# siren.net
KiCad netlist of a schematic drawn in EAGLE
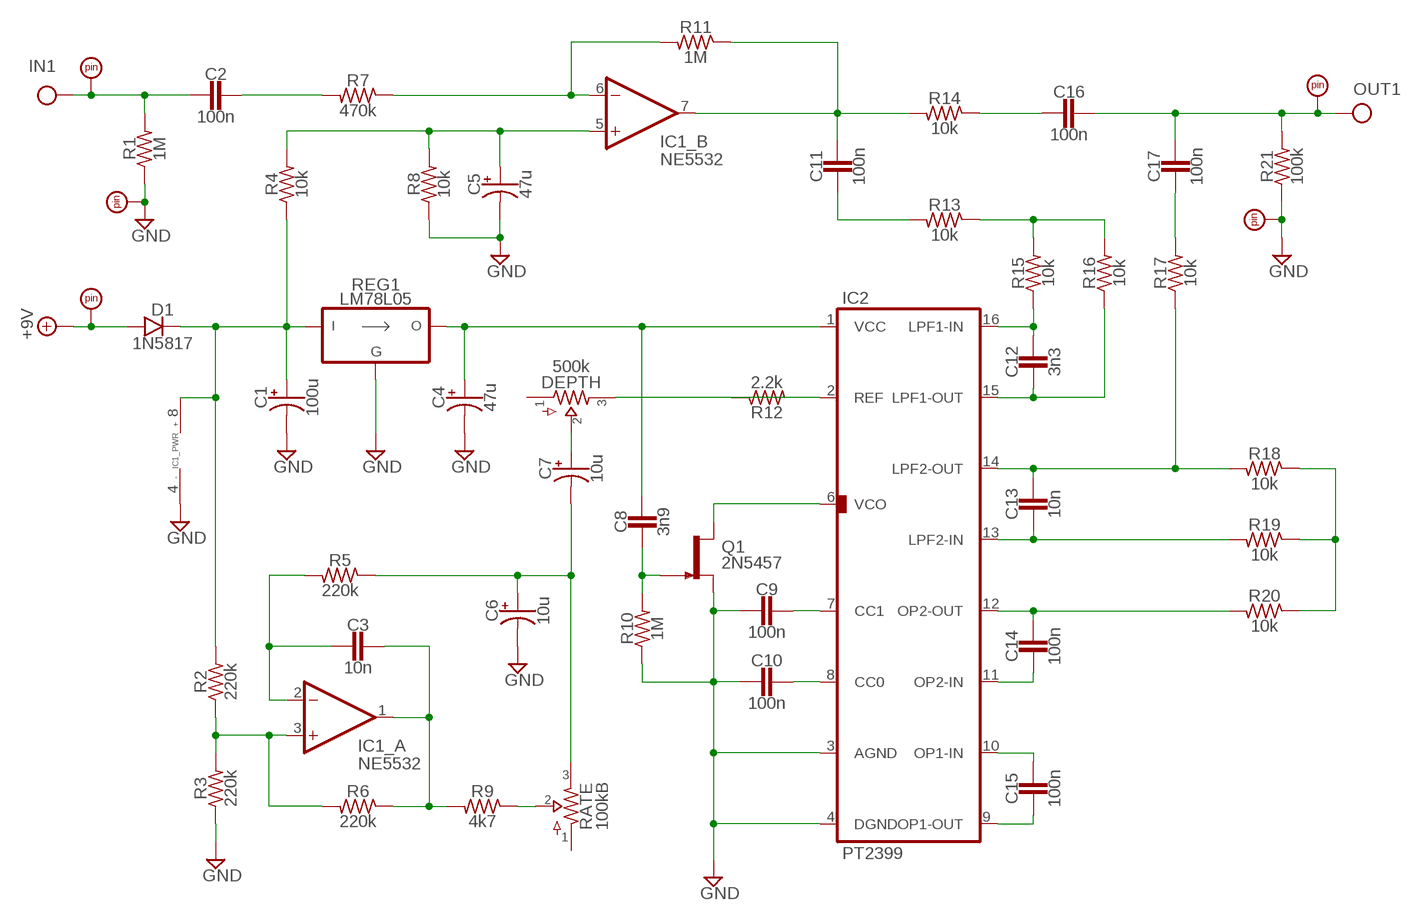
[diagram p0: schematic, sheet 1]

(export (version "E")
  (design (tool "Eeschema 10.0.6"))
  (components
    (comp (ref "C1")
      (value "100u")
      (footprint "eagle-import:050_020_1")
      (libsource (lib "eagle-import") (part "0501"))
    )
    (comp (ref "C2")
      (value "100n")
      (footprint "eagle-import:BOX_SMALL")
      (libsource (lib "eagle-import") (part "CER/FILMBOX.1"))
    )
    (comp (ref "C3")
      (value "10n")
      (footprint "eagle-import:BOX_SMALL")
      (libsource (lib "eagle-import") (part "CER/FILMBOX.1"))
    )
    (comp (ref "C4")
      (value "47u")
      (footprint "eagle-import:050_020_1")
      (libsource (lib "eagle-import") (part "0501"))
    )
    (comp (ref "C5")
      (value "47u")
      (footprint "eagle-import:050_020_1")
      (libsource (lib "eagle-import") (part "0501"))
    )
    (comp (ref "C6")
      (value "10u")
      (footprint "eagle-import:050_020_1")
      (libsource (lib "eagle-import") (part "0501"))
    )
    (comp (ref "C7")
      (value "10u")
      (footprint "eagle-import:050_020_1")
      (libsource (lib "eagle-import") (part "0501"))
    )
    (comp (ref "C8")
      (value "3n9")
      (footprint "eagle-import:BOX_SMALL")
      (libsource (lib "eagle-import") (part "CER/FILMBOX.1"))
    )
    (comp (ref "C9")
      (value "100n")
      (footprint "eagle-import:BOX_SMALL")
      (libsource (lib "eagle-import") (part "CER/FILMBOX.1"))
    )
    (comp (ref "C10")
      (value "100n")
      (footprint "eagle-import:BOX_SMALL")
      (libsource (lib "eagle-import") (part "CER/FILMBOX.1"))
    )
    (comp (ref "C11")
      (value "100n")
      (footprint "eagle-import:BOX_SMALL")
      (libsource (lib "eagle-import") (part "CER/FILMBOX.1"))
    )
    (comp (ref "C12")
      (value "3n3")
      (footprint "eagle-import:BOX_SMALL")
      (libsource (lib "eagle-import") (part "CER/FILMBOX.1"))
    )
    (comp (ref "C13")
      (value "10n")
      (footprint "eagle-import:BOX_SMALL")
      (libsource (lib "eagle-import") (part "CER/FILMBOX.1"))
    )
    (comp (ref "C14")
      (value "100n")
      (footprint "eagle-import:BOX_SMALL")
      (libsource (lib "eagle-import") (part "CER/FILMBOX.1"))
    )
    (comp (ref "C15")
      (value "100n")
      (footprint "eagle-import:BOX_SMALL")
      (libsource (lib "eagle-import") (part "CER/FILMBOX.1"))
    )
    (comp (ref "C16")
      (value "100n")
      (footprint "eagle-import:BOX_SMALL")
      (libsource (lib "eagle-import") (part "CER/FILMBOX.1"))
    )
    (comp (ref "C17")
      (value "100n")
      (footprint "eagle-import:BOX_SMALL")
      (libsource (lib "eagle-import") (part "CER/FILMBOX.1"))
    )
    (comp (ref "D1")
      (value "1N5817")
      (footprint "eagle-import:DO41-2")
      (libsource (lib "eagle-import") (part "DO41.2"))
    )
    (comp (ref "DEPTH")
      (value "500k")
      (footprint "eagle-import:2262_TRIM")
      (libsource (lib "eagle-import") (part "POTSTRIM"))
    )
    (comp (ref "IC1")
      (value "NE5532")
      (footprint "eagle-import:DIL08")
      (libsource (lib "eagle-import") (part "DUALTH"))
    )
    (comp (ref "IC2")
      (value "PT2399")
      (footprint "eagle-import:DIL16")
      (libsource (lib "eagle-import") (part "PT2399TH"))
    )
    (comp (ref "PAD1")
      (value "PADSQR")
      (footprint "eagle-import:SQUARE")
      (libsource (lib "eagle-import") (part "PADSQR"))
    )
    (comp (ref "PAD2")
      (value "PADSQR")
      (footprint "eagle-import:SQUARE")
      (libsource (lib "eagle-import") (part "PADSQR"))
    )
    (comp (ref "PAD3")
      (value "PADRND")
      (footprint "eagle-import:ROUND")
      (libsource (lib "eagle-import") (part "PADRND"))
    )
    (comp (ref "PAD4")
      (value "PADRND")
      (footprint "eagle-import:ROUND")
      (libsource (lib "eagle-import") (part "PADRND"))
    )
    (comp (ref "PAD5")
      (value "PADSQR")
      (footprint "eagle-import:SQUARE")
      (libsource (lib "eagle-import") (part "PADSQR"))
    )
    (comp (ref "Q1")
      (value "2N5457")
      (footprint "eagle-import:TO92-")
      (libsource (lib "eagle-import") (part "2N5457"))
    )
    (comp (ref "R1")
      (value "1M")
      (footprint "eagle-import:R0207_2V")
      (libsource (lib "eagle-import") (part "R_.2"))
    )
    (comp (ref "R2")
      (value "220k")
      (footprint "eagle-import:R0207_2V")
      (libsource (lib "eagle-import") (part "R_.2"))
    )
    (comp (ref "R3")
      (value "220k")
      (footprint "eagle-import:R0207_2V")
      (libsource (lib "eagle-import") (part "R_.2"))
    )
    (comp (ref "R4")
      (value "10k")
      (footprint "eagle-import:R0207_2V")
      (libsource (lib "eagle-import") (part "R_.2"))
    )
    (comp (ref "R5")
      (value "220k")
      (footprint "eagle-import:R0207_2V")
      (libsource (lib "eagle-import") (part "R_.2"))
    )
    (comp (ref "R6")
      (value "220k")
      (footprint "eagle-import:R0207_2V")
      (libsource (lib "eagle-import") (part "R_.2"))
    )
    (comp (ref "R7")
      (value "470k")
      (footprint "eagle-import:R0207_2V")
      (libsource (lib "eagle-import") (part "R_.2"))
    )
    (comp (ref "R8")
      (value "10k")
      (footprint "eagle-import:R0207_2V")
      (libsource (lib "eagle-import") (part "R_.2"))
    )
    (comp (ref "R9")
      (value "4k7")
      (footprint "eagle-import:R0207_2V")
      (libsource (lib "eagle-import") (part "R_.2"))
    )
    (comp (ref "R10")
      (value "1M")
      (footprint "eagle-import:R0207_2V")
      (libsource (lib "eagle-import") (part "R_.2"))
    )
    (comp (ref "R11")
      (value "1M")
      (footprint "eagle-import:R0207_2V")
      (libsource (lib "eagle-import") (part "R_.2"))
    )
    (comp (ref "R12")
      (value "2.2k")
      (footprint "eagle-import:R0207_2V")
      (libsource (lib "eagle-import") (part "R_.2"))
    )
    (comp (ref "R13")
      (value "10k")
      (footprint "eagle-import:R0207_2V")
      (libsource (lib "eagle-import") (part "R_.2"))
    )
    (comp (ref "R14")
      (value "10k")
      (footprint "eagle-import:R0207_2V")
      (libsource (lib "eagle-import") (part "R_.2"))
    )
    (comp (ref "R15")
      (value "10k")
      (footprint "eagle-import:R0207_2V")
      (libsource (lib "eagle-import") (part "R_.2"))
    )
    (comp (ref "R16")
      (value "10k")
      (footprint "eagle-import:R0207_2V")
      (libsource (lib "eagle-import") (part "R_.2"))
    )
    (comp (ref "R17")
      (value "10k")
      (footprint "eagle-import:R0207_2V")
      (libsource (lib "eagle-import") (part "R_.2"))
    )
    (comp (ref "R18")
      (value "10k")
      (footprint "eagle-import:R0207_2V")
      (libsource (lib "eagle-import") (part "R_.2"))
    )
    (comp (ref "R19")
      (value "10k")
      (footprint "eagle-import:R0207_2V")
      (libsource (lib "eagle-import") (part "R_.2"))
    )
    (comp (ref "R20")
      (value "10k")
      (footprint "eagle-import:R0207_2V")
      (libsource (lib "eagle-import") (part "R_.2"))
    )
    (comp (ref "R21")
      (value "100k")
      (footprint "eagle-import:R0207_2V")
      (libsource (lib "eagle-import") (part "R_.2"))
    )
    (comp (ref "RATE")
      (value "100kB")
      (footprint "eagle-import:PADS_SMALL")
      (libsource (lib "eagle-import") (part "POTSSMALL_PADS"))
    )
    (comp (ref "REG1")
      (value "LM78L05")
      (footprint "eagle-import:TO92-")
      (libsource (lib "eagle-import") (part "LM78L05"))
    )
  )
  (nets
    (net (code "1") (name "+9V") (class "Default")
      (node (ref "D1") (pin "A") (pinfunction "A_A") (pintype "passive"))
      (node (ref "PAD2") (pin "1") (pinfunction "P$1_1") (pintype "bidirectional"))
    )
    (net (code "2") (name "GND") (class "Default")
      (node (ref "C1") (pin "-") (pinfunction "-_-") (pintype "passive"))
      (node (ref "C10") (pin "2") (pinfunction "2_2") (pintype "passive"))
      (node (ref "C4") (pin "-") (pinfunction "-_-") (pintype "passive"))
      (node (ref "C5") (pin "-") (pinfunction "-_-") (pintype "passive"))
      (node (ref "C6") (pin "-") (pinfunction "-_-") (pintype "passive"))
      (node (ref "C9") (pin "2") (pinfunction "2_2") (pintype "passive"))
      (node (ref "IC1") (pin "4") (pinfunction "V-_4") (pintype "power_in"))
      (node (ref "IC2") (pin "3") (pinfunction "AGND_3") (pintype "power_in"))
      (node (ref "IC2") (pin "4") (pinfunction "DGND_4") (pintype "power_in"))
      (node (ref "PAD3") (pin "1") (pinfunction "P$1_1") (pintype "bidirectional"))
      (node (ref "PAD4") (pin "1") (pinfunction "P$1_1") (pintype "bidirectional"))
      (node (ref "Q1") (pin "2") (pinfunction "S_2") (pintype "passive"))
      (node (ref "R1") (pin "1") (pinfunction "1_1") (pintype "passive"))
      (node (ref "R10") (pin "1") (pinfunction "1_1") (pintype "passive"))
      (node (ref "R21") (pin "1") (pinfunction "1_1") (pintype "passive"))
      (node (ref "R3") (pin "1") (pinfunction "1_1") (pintype "passive"))
      (node (ref "R8") (pin "1") (pinfunction "1_1") (pintype "passive"))
      (node (ref "REG1") (pin "2") (pinfunction "GND_2") (pintype "passive"))
    )
    (net (code "3") (name "IN") (class "Default")
      (node (ref "C2") (pin "2") (pinfunction "2_2") (pintype "passive"))
      (node (ref "PAD1") (pin "1") (pinfunction "P$1_1") (pintype "bidirectional"))
      (node (ref "R1") (pin "2") (pinfunction "2_2") (pintype "passive"))
    )
    (net (code "4") (name "Net-(C2-Pad1)") (class "Default")
      (node (ref "C2") (pin "1") (pinfunction "1_1") (pintype "passive"))
      (node (ref "R7") (pin "2") (pinfunction "2_2") (pintype "passive"))
    )
    (net (code "5") (name "Net-(C6-Pad+)") (class "Default")
      (node (ref "C6") (pin "+") (pinfunction "+_+") (pintype "passive"))
      (node (ref "C7") (pin "-") (pinfunction "-_-") (pintype "passive"))
      (node (ref "R5") (pin "1") (pinfunction "1_1") (pintype "passive"))
      (node (ref "RATE") (pin "3") (pinfunction "3_3") (pintype "passive"))
    )
    (net (code "6") (name "Net-(C7-Pad+)") (class "Default")
      (node (ref "C7") (pin "+") (pinfunction "+_+") (pintype "passive"))
      (node (ref "DEPTH") (pin "2") (pinfunction "2_2") (pintype "passive"))
    )
    (net (code "7") (name "Net-(C11-Pad2)") (class "Default")
      (node (ref "C11") (pin "2") (pinfunction "2_2") (pintype "passive"))
      (node (ref "R13") (pin "2") (pinfunction "2_2") (pintype "passive"))
    )
    (net (code "8") (name "Net-(C16-Pad2)") (class "Default")
      (node (ref "C16") (pin "2") (pinfunction "2_2") (pintype "passive"))
      (node (ref "R14") (pin "1") (pinfunction "1_1") (pintype "passive"))
    )
    (net (code "9") (name "Net-(C17-Pad2)") (class "Default")
      (node (ref "C17") (pin "2") (pinfunction "2_2") (pintype "passive"))
      (node (ref "R17") (pin "2") (pinfunction "2_2") (pintype "passive"))
    )
    (net (code "10") (name "Net-(DEPTH-Pad3)") (class "Default")
      (node (ref "DEPTH") (pin "3") (pinfunction "3_3") (pintype "passive"))
      (node (ref "R12") (pin "2") (pinfunction "2_2") (pintype "passive"))
    )
    (net (code "11") (name "Net-(IC1A-+IN)") (class "Default")
      (node (ref "IC1") (pin "3") (pinfunction "+IN_3") (pintype "input"))
      (node (ref "R2") (pin "1") (pinfunction "1_1") (pintype "passive"))
      (node (ref "R3") (pin "2") (pinfunction "2_2") (pintype "passive"))
      (node (ref "R6") (pin "2") (pinfunction "2_2") (pintype "passive"))
    )
    (net (code "12") (name "Net-(IC1A--IN)") (class "Default")
      (node (ref "C3") (pin "2") (pinfunction "2_2") (pintype "passive"))
      (node (ref "IC1") (pin "2") (pinfunction "-IN_2") (pintype "input"))
      (node (ref "R5") (pin "2") (pinfunction "2_2") (pintype "passive"))
    )
    (net (code "13") (name "Net-(IC1A-OUT)") (class "Default")
      (node (ref "C3") (pin "1") (pinfunction "1_1") (pintype "passive"))
      (node (ref "IC1") (pin "1") (pinfunction "OUT_1") (pintype "output"))
      (node (ref "R6") (pin "1") (pinfunction "1_1") (pintype "passive"))
      (node (ref "R9") (pin "2") (pinfunction "2_2") (pintype "passive"))
    )
    (net (code "14") (name "Net-(IC1B-+IN)") (class "Default")
      (node (ref "C5") (pin "+") (pinfunction "+_+") (pintype "passive"))
      (node (ref "IC1") (pin "5") (pinfunction "+IN_5") (pintype "input"))
      (node (ref "R4") (pin "2") (pinfunction "2_2") (pintype "passive"))
      (node (ref "R8") (pin "2") (pinfunction "2_2") (pintype "passive"))
    )
    (net (code "15") (name "Net-(IC1B--IN)") (class "Default")
      (node (ref "IC1") (pin "6") (pinfunction "-IN_6") (pintype "input"))
      (node (ref "R11") (pin "2") (pinfunction "2_2") (pintype "passive"))
      (node (ref "R7") (pin "1") (pinfunction "1_1") (pintype "passive"))
    )
    (net (code "16") (name "Net-(IC1B-OUT)") (class "Default")
      (node (ref "C11") (pin "1") (pinfunction "1_1") (pintype "passive"))
      (node (ref "IC1") (pin "7") (pinfunction "OUT_7") (pintype "output"))
      (node (ref "R11") (pin "1") (pinfunction "1_1") (pintype "passive"))
      (node (ref "R14") (pin "2") (pinfunction "2_2") (pintype "passive"))
    )
    (net (code "17") (name "Net-(IC1C-V+)") (class "Default")
      (node (ref "C1") (pin "+") (pinfunction "+_+") (pintype "passive"))
      (node (ref "D1") (pin "C") (pinfunction "C_C") (pintype "passive"))
      (node (ref "IC1") (pin "8") (pinfunction "V+_8") (pintype "power_in"))
      (node (ref "R2") (pin "2") (pinfunction "2_2") (pintype "passive"))
      (node (ref "R4") (pin "1") (pinfunction "1_1") (pintype "passive"))
      (node (ref "REG1") (pin "1") (pinfunction "VI_1") (pintype "input"))
    )
    (net (code "18") (name "Net-(IC2-CC0)") (class "Default")
      (node (ref "C10") (pin "1") (pinfunction "1_1") (pintype "passive"))
      (node (ref "IC2") (pin "8") (pinfunction "CC0_8") (pintype "input"))
    )
    (net (code "19") (name "Net-(IC2-CC1)") (class "Default")
      (node (ref "C9") (pin "1") (pinfunction "1_1") (pintype "passive"))
      (node (ref "IC2") (pin "7") (pinfunction "CC1_7") (pintype "input"))
    )
    (net (code "20") (name "Net-(IC2-LPF1-IN)") (class "Default")
      (node (ref "C12") (pin "1") (pinfunction "1_1") (pintype "passive"))
      (node (ref "IC2") (pin "16") (pinfunction "LPF1-IN_16") (pintype "input"))
      (node (ref "R15") (pin "1") (pinfunction "1_1") (pintype "passive"))
    )
    (net (code "21") (name "Net-(IC2-LPF1-OUT)") (class "Default")
      (node (ref "C12") (pin "2") (pinfunction "2_2") (pintype "passive"))
      (node (ref "IC2") (pin "15") (pinfunction "LPF1-OUT_15") (pintype "output"))
      (node (ref "R16") (pin "1") (pinfunction "1_1") (pintype "passive"))
    )
    (net (code "22") (name "Net-(IC2-LPF2-IN)") (class "Default")
      (node (ref "C13") (pin "2") (pinfunction "2_2") (pintype "passive"))
      (node (ref "IC2") (pin "13") (pinfunction "LPF2-IN_13") (pintype "input"))
      (node (ref "R19") (pin "2") (pinfunction "2_2") (pintype "passive"))
    )
    (net (code "23") (name "Net-(IC2-LPF2-OUT)") (class "Default")
      (node (ref "C13") (pin "1") (pinfunction "1_1") (pintype "passive"))
      (node (ref "IC2") (pin "14") (pinfunction "LPF2-OUT_14") (pintype "output"))
      (node (ref "R17") (pin "1") (pinfunction "1_1") (pintype "passive"))
      (node (ref "R18") (pin "2") (pinfunction "2_2") (pintype "passive"))
    )
    (net (code "24") (name "Net-(IC2-OP1-IN)") (class "Default")
      (node (ref "C15") (pin "1") (pinfunction "1_1") (pintype "passive"))
      (node (ref "IC2") (pin "10") (pinfunction "OP1-IN_10") (pintype "input"))
    )
    (net (code "25") (name "Net-(IC2-OP1-OUT)") (class "Default")
      (node (ref "C15") (pin "2") (pinfunction "2_2") (pintype "passive"))
      (node (ref "IC2") (pin "9") (pinfunction "OP1-OUT_9") (pintype "output"))
    )
    (net (code "26") (name "Net-(IC2-OP2-IN)") (class "Default")
      (node (ref "C14") (pin "2") (pinfunction "2_2") (pintype "passive"))
      (node (ref "IC2") (pin "11") (pinfunction "OP2-IN_11") (pintype "input"))
    )
    (net (code "27") (name "Net-(IC2-OP2-OUT)") (class "Default")
      (node (ref "C14") (pin "1") (pinfunction "1_1") (pintype "passive"))
      (node (ref "IC2") (pin "12") (pinfunction "OP2-OUT_12") (pintype "output"))
      (node (ref "R20") (pin "2") (pinfunction "2_2") (pintype "passive"))
    )
    (net (code "28") (name "Net-(IC2-REF)") (class "Default")
      (node (ref "IC2") (pin "2") (pinfunction "REF_2") (pintype "input"))
      (node (ref "R12") (pin "1") (pinfunction "1_1") (pintype "passive"))
    )
    (net (code "29") (name "Net-(IC2-VCC)") (class "Default")
      (node (ref "C4") (pin "+") (pinfunction "+_+") (pintype "passive"))
      (node (ref "C8") (pin "1") (pinfunction "1_1") (pintype "passive"))
      (node (ref "IC2") (pin "1") (pinfunction "VCC_1") (pintype "power_in"))
      (node (ref "REG1") (pin "3") (pinfunction "VO_3") (pintype "passive"))
    )
    (net (code "30") (name "Net-(IC2-VCO)") (class "Default")
      (node (ref "IC2") (pin "6") (pinfunction "VCO_6") (pintype "input"))
      (node (ref "Q1") (pin "3") (pinfunction "D_3") (pintype "passive"))
    )
    (net (code "31") (name "Net-(Q1-G)") (class "Default")
      (node (ref "C8") (pin "2") (pinfunction "2_2") (pintype "passive"))
      (node (ref "Q1") (pin "1") (pinfunction "G_1") (pintype "passive"))
      (node (ref "R10") (pin "2") (pinfunction "2_2") (pintype "passive"))
    )
    (net (code "32") (name "Net-(R9-Pad1)") (class "Default")
      (node (ref "R9") (pin "1") (pinfunction "1_1") (pintype "passive"))
      (node (ref "RATE") (pin "2") (pinfunction "2_2") (pintype "passive"))
    )
    (net (code "33") (name "Net-(R13-Pad1)") (class "Default")
      (node (ref "R13") (pin "1") (pinfunction "1_1") (pintype "passive"))
      (node (ref "R15") (pin "2") (pinfunction "2_2") (pintype "passive"))
      (node (ref "R16") (pin "2") (pinfunction "2_2") (pintype "passive"))
    )
    (net (code "34") (name "Net-(R18-Pad1)") (class "Default")
      (node (ref "R18") (pin "1") (pinfunction "1_1") (pintype "passive"))
      (node (ref "R19") (pin "1") (pinfunction "1_1") (pintype "passive"))
      (node (ref "R20") (pin "1") (pinfunction "1_1") (pintype "passive"))
    )
    (net (code "35") (name "OUT") (class "Default")
      (node (ref "C16") (pin "1") (pinfunction "1_1") (pintype "passive"))
      (node (ref "C17") (pin "1") (pinfunction "1_1") (pintype "passive"))
      (node (ref "PAD5") (pin "1") (pinfunction "P$1_1") (pintype "bidirectional"))
      (node (ref "R21") (pin "2") (pinfunction "2_2") (pintype "passive"))
    )
    (net (code "36") (name "unconnected-(DEPTH-Pad1)") (class "Default")
      (node (ref "DEPTH") (pin "1") (pinfunction "1_1") (pintype "passive"))
    )
    (net (code "37") (name "unconnected-(RATE-Pad1)") (class "Default")
      (node (ref "RATE") (pin "1") (pinfunction "1_1") (pintype "passive"))
    )
  )
)
